# 555_timer.net
KiCad netlist of a schematic drawn in Altium Designer
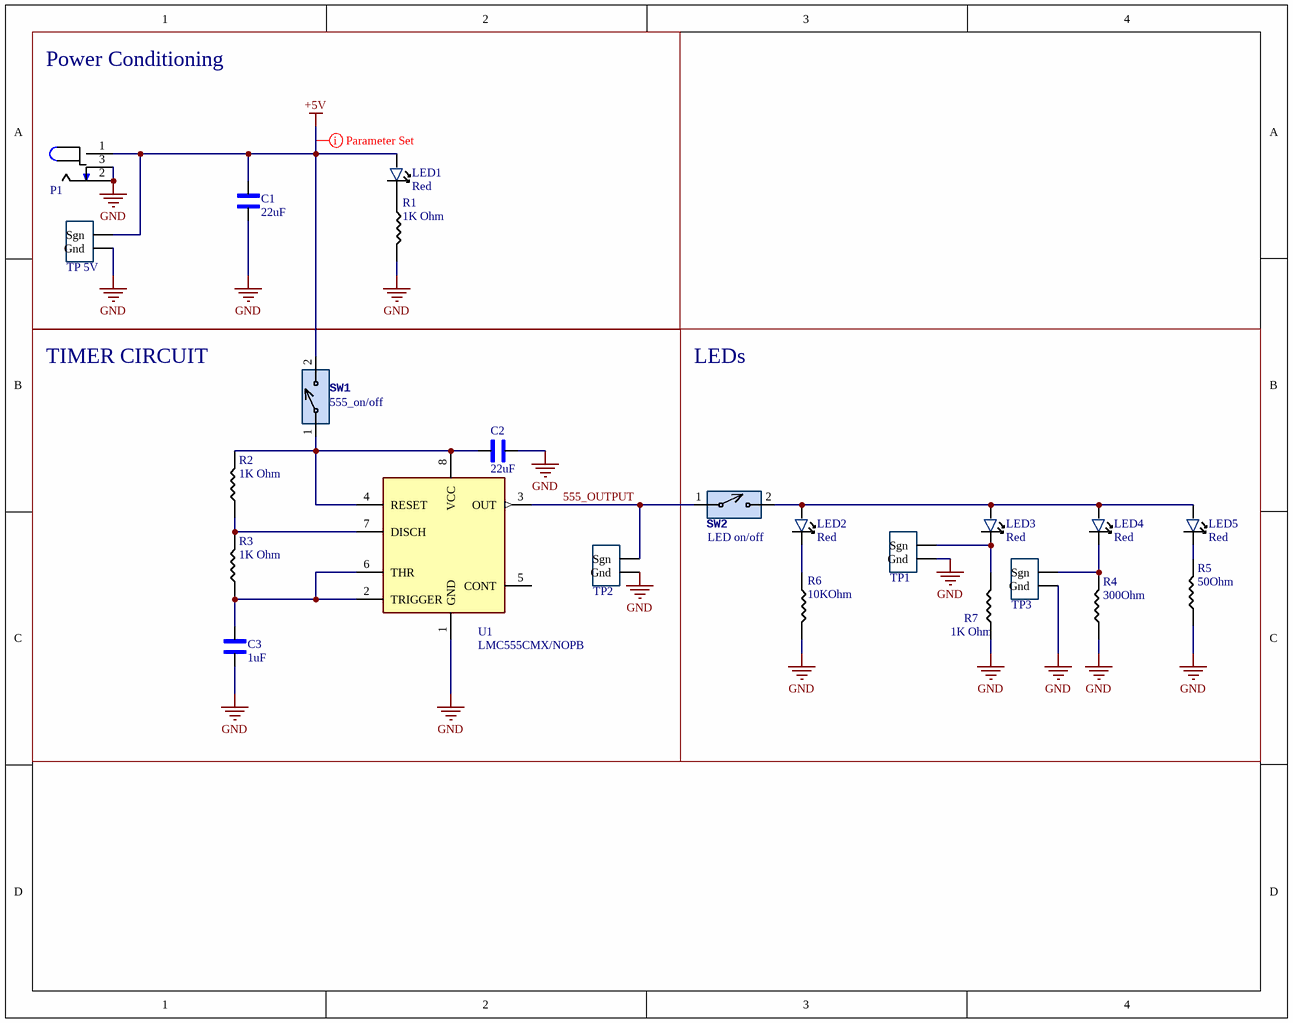
[diagram p0: 555_timer.SchDoc]

(export (version "E")
  (design (tool "Eeschema 10.0.6"))
  (components
    (comp (ref "C1")
      (value "22uF")
      (footprint "1206_Passive_Capacitor")
      (description "22uF ±10% 25V X5R 1206 Multilayer Ceramic Capacitors MLCC - SMD/SMT RoHS")
      (fields (field (name "MFR PART #") "CL31A226KAHNNNE") (field (name "LCSC PART#") "C12891"))
      (libsource (lib "ECEN5730Lib_2023_05_DS") (part "C_22uF_1206"))
    )
    (comp (ref "C2")
      (value "22uF")
      (footprint "1206_Passive_Capacitor")
      (description "22uF ±10% 25V X5R 1206 Multilayer Ceramic Capacitors MLCC - SMD/SMT RoHS")
      (fields (field (name "MFR PART #") "CL31A226KAHNNNE") (field (name "LCSC PART#") "C12891"))
      (libsource (lib "ECEN5730Lib_2023_05_DS") (part "C_22uF_1206"))
    )
    (comp (ref "C3")
      (value "1uF")
      (footprint "1206_Passive_Capacitor")
      (description "MULTILAYER CERAMIC CAPACITORS MLCC - SMD/SMT 1UF 50V 1206 ROHS")
      (fields (field (name "MFR PART #") "CL31B105KBHNNNE") (field (name "LCSC PART#") "C1848"))
      (libsource (lib "ECEN5730Lib_2023_05_DS") (part "C_1uF_1206"))
    )
    (comp (ref "LED1")
      (value "Red")
      (footprint "LED_1206")
      (description "Red 621~631nm 1206 Light Emitting Diodes (LED) RoHS")
      (fields (field (name "MFR PART #") "15-21/R6C-FQ1R1B/2T") (field (name "LCSC PART#") "C93133"))
      (libsource (lib "ECEN5730Lib_2023_05_DS") (part "LED_RED_1206"))
    )
    (comp (ref "LED2")
      (value "Red")
      (footprint "LED_1206")
      (description "Red 621~631nm 1206 Light Emitting Diodes (LED) RoHS")
      (fields (field (name "MFR PART #") "15-21/R6C-FQ1R1B/2T") (field (name "LCSC PART#") "C93133"))
      (libsource (lib "ECEN5730Lib_2023_05_DS") (part "LED_RED_1206"))
    )
    (comp (ref "LED3")
      (value "Red")
      (footprint "LED_1206")
      (description "Red 621~631nm 1206 Light Emitting Diodes (LED) RoHS")
      (fields (field (name "MFR PART #") "15-21/R6C-FQ1R1B/2T") (field (name "LCSC PART#") "C93133"))
      (libsource (lib "ECEN5730Lib_2023_05_DS") (part "LED_RED_1206"))
    )
    (comp (ref "LED4")
      (value "Red")
      (footprint "LED_1206")
      (description "Red 621~631nm 1206 Light Emitting Diodes (LED) RoHS")
      (fields (field (name "MFR PART #") "15-21/R6C-FQ1R1B/2T") (field (name "LCSC PART#") "C93133"))
      (libsource (lib "ECEN5730Lib_2023_05_DS") (part "LED_RED_1206"))
    )
    (comp (ref "LED5")
      (value "Red")
      (footprint "LED_1206")
      (description "Red 621~631nm 1206 Light Emitting Diodes (LED) RoHS")
      (fields (field (name "MFR PART #") "15-21/R6C-FQ1R1B/2T") (field (name "LCSC PART#") "C93133"))
      (libsource (lib "ECEN5730Lib_2023_05_DS") (part "LED_RED_1206"))
    )
    (comp (ref "P1")
      (value "Power Jack")
      (footprint "Power_Jack")
      (description "Power Barrel Connector Jack 2.10mm ID (0.083\"), 5.50mm OD (0.217\") Through Hole, Right Angle")
      (fields (field (name "MFR PART #") "PJ-102A") (field (name "LCSC PART#") "C136744"))
      (libsource (lib "ECEN5730Lib_2023_05_DS") (part "P_Power Jack"))
    )
    (comp (ref "R1")
      (value "1K Ohm")
      (footprint "1206_Passive_Resitor")
      (description "CHIP RESISTOR - SURFACE MOUNT 1KOHMS ±1% 1/4W 1206 ROHS")
      (fields (field (name "MFR PART #") "RNCP1206FTD1K00CT") (field (name "LCSC PART#") "C4410"))
      (libsource (lib "ECEN5730Lib_2023_05_DS") (part "R_1K_1206"))
    )
    (comp (ref "R2")
      (value "1K Ohm")
      (footprint "1206_Passive_Resitor")
      (description "CHIP RESISTOR - SURFACE MOUNT 1KOHMS ±1% 1/4W 1206 ROHS")
      (fields (field (name "MFR PART #") "RNCP1206FTD1K00CT") (field (name "LCSC PART#") "C4410"))
      (libsource (lib "ECEN5730Lib_2023_05_DS") (part "R_1K_1206"))
    )
    (comp (ref "R3")
      (value "1K Ohm")
      (footprint "1206_Passive_Resitor")
      (description "CHIP RESISTOR - SURFACE MOUNT 1KOHMS ±1% 1/4W 1206 ROHS")
      (fields (field (name "MFR PART #") "RNCP1206FTD1K00CT") (field (name "LCSC PART#") "C4410"))
      (libsource (lib "ECEN5730Lib_2023_05_DS") (part "R_1K_1206"))
    )
    (comp (ref "R4")
      (value "300Ohm")
      (footprint "1206_Passive_Resitor")
      (description "CHIP RESISTOR - SURFACE MOUNT 300OHMS ±1% 1/4W 1206 ROHS")
      (fields (field (name "MFR PART #") "1206W4F3000T5E") (field (name "LCSC PART#") "C17887"))
      (libsource (lib "ECEN5730Lib_2023_05_DS") (part "R_300Ohm_1206"))
    )
    (comp (ref "R5")
      (value "50Ohm")
      (footprint "1206_Passive_Resitor")
      (description "100Ω ±1% 0.25W ±100ppm/℃ 1206 Chip Resistor - Surface Mount RoHS")
      (fields (field (name "LCSC PART#") "C17901") (field (name "MFR PART #") "1206W4F1000T5E"))
      (libsource (lib "ECEN5730Lib_2023_05_DS") (part "R_100Ohm_1206"))
    )
    (comp (ref "R6")
      (value "10KOhm")
      (footprint "1206_Passive_Resitor")
      (description "10 kOhms ±5% 0.25W, 1/4W Chip Resistor 1206 (3216 Metric) Automotive AEC-Q200 Thick Film")
      (fields (field (name "MFR PART #") "RMCF1206FT10K0") (field (name "LCSC PART#") "C17902"))
      (libsource (lib "ECEN5730Lib_2023_05_DS") (part "R_10KOhm_1206"))
    )
    (comp (ref "R7")
      (value "1K Ohm")
      (footprint "1206_Passive_Resitor")
      (description "CHIP RESISTOR - SURFACE MOUNT 1KOHMS ±1% 1/4W 1206 ROHS")
      (fields (field (name "MFR PART #") "RNCP1206FTD1K00CT") (field (name "LCSC PART#") "C4410"))
      (libsource (lib "ECEN5730Lib_2023_05_DS") (part "R_1K_1206"))
    )
    (comp (ref "SW1")
      (value "SW_2Pin_100mil_Switch")
      (footprint "2Pin-Header-Conn")
      (description "2Pin Header")
      (fields (field (name "LCSC PART#") "C124375"))
      (libsource (lib "") (part "SW_2Pin_100mil_Switch_1"))
    )
    (comp (ref "SW2")
      (value "SW_2Pin_100mil_Switch")
      (footprint "2Pin-Header-Conn")
      (description "2Pin Header")
      (fields (field (name "LCSC PART#") "C124375"))
      (libsource (lib "ECEN5730Lib_2023_05_DS") (part "SW_2Pin_100mil_Switch"))
    )
    (comp (ref "TP 5V")
      (value "10x Probe TP")
      (footprint "TP10x_Probe")
      (description "Test Point 300 mil centers")
      (libsource (lib "ECEN5730Lib_2023_05_DS") (part "TP_10x_Probe"))
    )
    (comp (ref "TP1")
      (value "10x Probe TP")
      (footprint "TP10x_Probe")
      (description "Test Point 300 mil centers")
      (libsource (lib "ECEN5730Lib_2023_05_DS") (part "TP_10x_Probe"))
    )
    (comp (ref "TP2")
      (value "10x Probe TP")
      (footprint "TP10x_Probe")
      (description "Test Point 300 mil centers")
      (libsource (lib "ECEN5730Lib_2023_05_DS") (part "TP_10x_Probe"))
    )
    (comp (ref "TP3")
      (value "10x Probe TP")
      (footprint "TP10x_Probe")
      (description "Test Point 300 mil centers")
      (libsource (lib "ECEN5730Lib_2023_05_DS") (part "TP_10x_Probe"))
    )
    (comp (ref "U1")
      (value "LMC555CMX/NOPB")
      (footprint "TS555IDTTR")
      (description "555 Type, Timer/Oscillator _Single_ IC 3MHz 8-SO")
      (fields (field (name "LCSC PART#") "C90760"))
      (libsource (lib "ECEN5730Lib_2023_05_DS") (part "U_555_Fast"))
    )
  )
  (nets
    (net (code "1") (name "+5V") (class "Default")
      (node (ref "C1") (pin "2") (pinfunction "2_2") (pintype "passive"))
      (node (ref "LED1") (pin "1") (pinfunction "1_1") (pintype "passive"))
      (node (ref "P1") (pin "1") (pinfunction "1_1") (pintype "power_in"))
      (node (ref "SW1") (pin "2") (pinfunction "2_2") (pintype "passive"))
      (node (ref "TP 5V") (pin "1") (pinfunction "Sgn_1") (pintype "passive"))
    )
    (net (code "2") (name "/555_OUTPUT") (class "Default")
      (node (ref "SW2") (pin "1") (pinfunction "1_1") (pintype "passive"))
      (node (ref "TP2") (pin "1") (pinfunction "Sgn_1") (pintype "passive"))
      (node (ref "U1") (pin "3") (pinfunction "OUT_3") (pintype "output"))
    )
    (net (code "3") (name "GND") (class "Default")
      (node (ref "C1") (pin "1") (pinfunction "1_1") (pintype "passive"))
      (node (ref "C2") (pin "1") (pinfunction "1_1") (pintype "passive"))
      (node (ref "C3") (pin "1") (pinfunction "1_1") (pintype "passive"))
      (node (ref "P1") (pin "2") (pinfunction "2_2") (pintype "power_in"))
      (node (ref "P1") (pin "3") (pinfunction "3_3") (pintype "power_in"))
      (node (ref "R1") (pin "2") (pinfunction "2_2") (pintype "passive"))
      (node (ref "R4") (pin "1") (pinfunction "1_1") (pintype "passive"))
      (node (ref "R5") (pin "1") (pinfunction "1_1") (pintype "passive"))
      (node (ref "R6") (pin "2") (pinfunction "2_2") (pintype "passive"))
      (node (ref "R7") (pin "1") (pinfunction "1_1") (pintype "passive"))
      (node (ref "TP 5V") (pin "2") (pinfunction "Gnd_2") (pintype "passive"))
      (node (ref "TP1") (pin "2") (pinfunction "Gnd_2") (pintype "passive"))
      (node (ref "TP2") (pin "2") (pinfunction "Gnd_2") (pintype "passive"))
      (node (ref "TP3") (pin "2") (pinfunction "Gnd_2") (pintype "passive"))
      (node (ref "U1") (pin "1") (pinfunction "GND_1") (pintype "power_in"))
    )
    (net (code "4") (name "Net-(LED1-Pad2)") (class "Default")
      (node (ref "LED1") (pin "2") (pinfunction "2_2") (pintype "passive"))
      (node (ref "R1") (pin "1") (pinfunction "1_1") (pintype "passive"))
    )
    (net (code "5") (name "Net-(LED2-Pad1)") (class "Default")
      (node (ref "LED2") (pin "1") (pinfunction "1_1") (pintype "passive"))
      (node (ref "LED3") (pin "1") (pinfunction "1_1") (pintype "passive"))
      (node (ref "LED4") (pin "1") (pinfunction "1_1") (pintype "passive"))
      (node (ref "LED5") (pin "1") (pinfunction "1_1") (pintype "passive"))
      (node (ref "SW2") (pin "2") (pinfunction "2_2") (pintype "passive"))
    )
    (net (code "6") (name "Net-(LED2-Pad2)") (class "Default")
      (node (ref "LED2") (pin "2") (pinfunction "2_2") (pintype "passive"))
      (node (ref "R6") (pin "1") (pinfunction "1_1") (pintype "passive"))
    )
    (net (code "7") (name "Net-(LED5-Pad2)") (class "Default")
      (node (ref "LED5") (pin "2") (pinfunction "2_2") (pintype "passive"))
      (node (ref "R5") (pin "2") (pinfunction "2_2") (pintype "passive"))
    )
    (net (code "8") (name "Net-(TP1-Sgn)") (class "Default")
      (node (ref "LED3") (pin "2") (pinfunction "2_2") (pintype "passive"))
      (node (ref "R7") (pin "2") (pinfunction "2_2") (pintype "passive"))
      (node (ref "TP1") (pin "1") (pinfunction "Sgn_1") (pintype "passive"))
    )
    (net (code "9") (name "Net-(TP3-Sgn)") (class "Default")
      (node (ref "LED4") (pin "2") (pinfunction "2_2") (pintype "passive"))
      (node (ref "R4") (pin "2") (pinfunction "2_2") (pintype "passive"))
      (node (ref "TP3") (pin "1") (pinfunction "Sgn_1") (pintype "passive"))
    )
    (net (code "10") (name "Net-(U1-DISCH)") (class "Default")
      (node (ref "R2") (pin "1") (pinfunction "1_1") (pintype "passive"))
      (node (ref "R3") (pin "2") (pinfunction "2_2") (pintype "passive"))
      (node (ref "U1") (pin "7") (pinfunction "DISCH_7") (pintype "passive"))
    )
    (net (code "11") (name "Net-(U1-RESET)") (class "Default")
      (node (ref "C2") (pin "2") (pinfunction "2_2") (pintype "passive"))
      (node (ref "R2") (pin "2") (pinfunction "2_2") (pintype "passive"))
      (node (ref "SW1") (pin "1") (pinfunction "1_1") (pintype "passive"))
      (node (ref "U1") (pin "4") (pinfunction "RESET_4") (pintype "passive"))
      (node (ref "U1") (pin "8") (pinfunction "VCC_8") (pintype "power_in"))
    )
    (net (code "12") (name "Net-(U1-THR)") (class "Default")
      (node (ref "C3") (pin "2") (pinfunction "2_2") (pintype "passive"))
      (node (ref "R3") (pin "1") (pinfunction "1_1") (pintype "passive"))
      (node (ref "U1") (pin "2") (pinfunction "TRIGGER_2") (pintype "passive"))
      (node (ref "U1") (pin "6") (pinfunction "THR_6") (pintype "passive"))
    )
    (net (code "13") (name "unconnected-(U1-CONT-Pad5)") (class "Default")
      (node (ref "U1") (pin "5") (pinfunction "CONT_5") (pintype "passive"))
    )
  )
)
